# msp430-nrf24.net
KiCad netlist of a schematic drawn in EAGLE
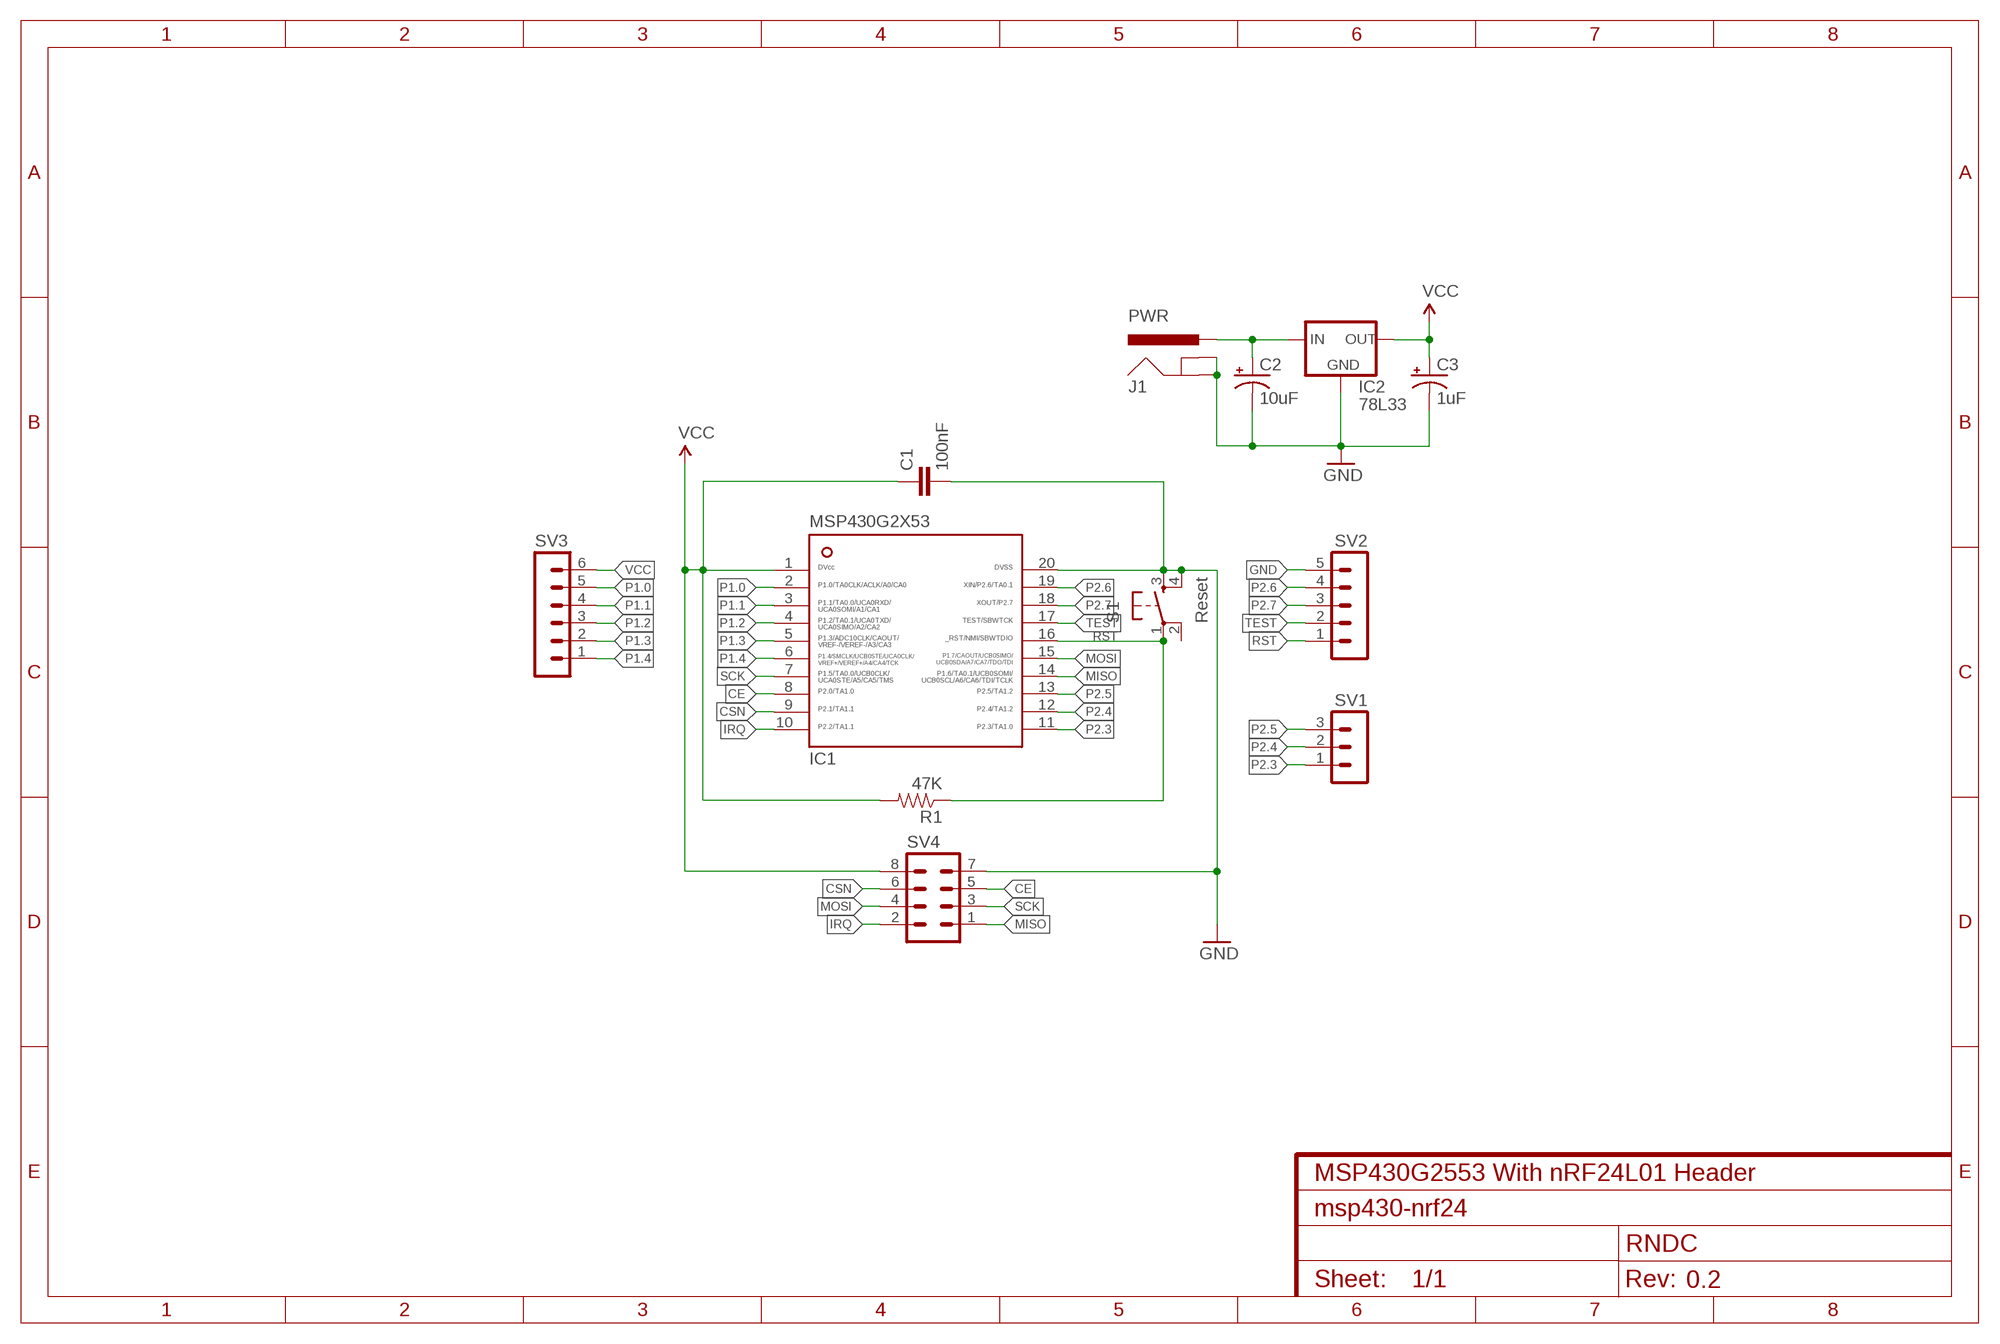
[diagram p0: schematic, sheet 1]

(export (version "E")
  (design (tool "Eeschema 10.0.6"))
  (components
    (comp (ref "C1")
      (value "100nF")
      (footprint "eagle-import:CAP-PTH-SMALL-KIT")
      (libsource (lib "eagle-import") (part "CAPKIT"))
    )
    (comp (ref "C2")
      (value "10uF")
      (footprint "eagle-import:CPOL-RADIAL-10UF-25V")
      (libsource (lib "eagle-import") (part "CAP_POLPTH2"))
    )
    (comp (ref "C3")
      (value "1uF")
      (footprint "eagle-import:CPOL-RADIAL-10UF-25V")
      (libsource (lib "eagle-import") (part "CAP_POLPTH2"))
    )
    (comp (ref "IC1")
      (value "MSP430G2X53-20N20")
      (footprint "eagle-import:N20")
      (libsource (lib "eagle-import") (part "MSP430G2X53-20N20"))
    )
    (comp (ref "IC2")
      (value "78L33")
      (footprint "eagle-import:TO-92")
      (libsource (lib "eagle-import") (part "V_REG_78XXTO-92_UNTESTED"))
    )
    (comp (ref "J1")
      (value "PWR")
      (footprint "eagle-import:POWER_JACK_PTH")
      (libsource (lib "eagle-import") (part "POWER_JACKPTH"))
    )
    (comp (ref "R1")
      (value "47K")
      (footprint "eagle-import:AXIAL-0.3-KIT")
      (libsource (lib "eagle-import") (part "RESISTORKIT"))
    )
    (comp (ref "S1")
      (value "Reset")
      (footprint "eagle-import:TACTILE-PTH")
      (libsource (lib "eagle-import") (part "TAC_SWITCHPTH"))
    )
    (comp (ref "SV1")
      (value "MA03-1")
      (footprint "eagle-import:MA03-1")
      (libsource (lib "eagle-import") (part "MA03-1"))
    )
    (comp (ref "SV2")
      (value "MA05-1")
      (footprint "eagle-import:MA05-1")
      (libsource (lib "eagle-import") (part "MA05-1"))
    )
    (comp (ref "SV3")
      (value "MA06-1")
      (footprint "eagle-import:MA06-1")
      (libsource (lib "eagle-import") (part "MA06-1"))
    )
    (comp (ref "SV4")
      (value "MA04-2")
      (footprint "eagle-import:MA04-2")
      (libsource (lib "eagle-import") (part "MA04-2"))
    )
  )
  (nets
    (net (code "1") (name "CE") (class "Default")
      (node (ref "IC1") (pin "8") (pinfunction "8_8") (pintype "bidirectional"))
      (node (ref "SV4") (pin "5") (pinfunction "5_5") (pintype "passive"))
    )
    (net (code "2") (name "CSN") (class "Default")
      (node (ref "IC1") (pin "9") (pinfunction "9_9") (pintype "bidirectional"))
      (node (ref "SV4") (pin "6") (pinfunction "6_6") (pintype "passive"))
    )
    (net (code "3") (name "GND") (class "Default")
      (node (ref "C1") (pin "2") (pinfunction "2_2") (pintype "passive"))
      (node (ref "C2") (pin "2") (pinfunction "-_2") (pintype "passive"))
      (node (ref "C3") (pin "2") (pinfunction "-_2") (pintype "passive"))
      (node (ref "IC1") (pin "20") (pinfunction "20_20") (pintype "bidirectional"))
      (node (ref "IC2") (pin "1") (pinfunction "GND_1") (pintype "input"))
      (node (ref "J1") (pin "GND") (pinfunction "GND_GND") (pintype "bidirectional"))
      (node (ref "J1") (pin "GNDBREAK") (pinfunction "GNDBREAK_GNDBREAK") (pintype "bidirectional"))
      (node (ref "S1") (pin "3") (pinfunction "3_3") (pintype "passive"))
      (node (ref "S1") (pin "4") (pinfunction "4_4") (pintype "passive"))
      (node (ref "SV2") (pin "5") (pinfunction "5_5") (pintype "passive"))
      (node (ref "SV4") (pin "7") (pinfunction "7_7") (pintype "passive"))
    )
    (net (code "4") (name "IRQ") (class "Default")
      (node (ref "IC1") (pin "10") (pinfunction "10_10") (pintype "bidirectional"))
      (node (ref "SV4") (pin "2") (pinfunction "2_2") (pintype "passive"))
    )
    (net (code "5") (name "MISO") (class "Default")
      (node (ref "IC1") (pin "14") (pinfunction "14_14") (pintype "bidirectional"))
      (node (ref "SV4") (pin "1") (pinfunction "1_1") (pintype "passive"))
    )
    (net (code "6") (name "MOSI") (class "Default")
      (node (ref "IC1") (pin "15") (pinfunction "15_15") (pintype "bidirectional"))
      (node (ref "SV4") (pin "4") (pinfunction "4_4") (pintype "passive"))
    )
    (net (code "7") (name "Net-(C2-+)") (class "Default")
      (node (ref "C2") (pin "1") (pinfunction "+_1") (pintype "passive"))
      (node (ref "IC2") (pin "2") (pinfunction "IN_2") (pintype "input"))
      (node (ref "J1") (pin "PWR") (pinfunction "PWR_PWR") (pintype "bidirectional"))
    )
    (net (code "8") (name "P1.0") (class "Default")
      (node (ref "IC1") (pin "2") (pinfunction "2_2") (pintype "bidirectional"))
      (node (ref "SV3") (pin "5") (pinfunction "5_5") (pintype "passive"))
    )
    (net (code "9") (name "P1.1") (class "Default")
      (node (ref "IC1") (pin "3") (pinfunction "3_3") (pintype "bidirectional"))
      (node (ref "SV3") (pin "4") (pinfunction "4_4") (pintype "passive"))
    )
    (net (code "10") (name "P1.2") (class "Default")
      (node (ref "IC1") (pin "4") (pinfunction "4_4") (pintype "bidirectional"))
      (node (ref "SV3") (pin "3") (pinfunction "3_3") (pintype "passive"))
    )
    (net (code "11") (name "P1.3") (class "Default")
      (node (ref "IC1") (pin "5") (pinfunction "5_5") (pintype "bidirectional"))
      (node (ref "SV3") (pin "2") (pinfunction "2_2") (pintype "passive"))
    )
    (net (code "12") (name "P1.4") (class "Default")
      (node (ref "IC1") (pin "6") (pinfunction "6_6") (pintype "bidirectional"))
      (node (ref "SV3") (pin "1") (pinfunction "1_1") (pintype "passive"))
    )
    (net (code "13") (name "P2.3") (class "Default")
      (node (ref "IC1") (pin "11") (pinfunction "11_11") (pintype "bidirectional"))
      (node (ref "SV1") (pin "1") (pinfunction "1_1") (pintype "passive"))
    )
    (net (code "14") (name "P2.4") (class "Default")
      (node (ref "IC1") (pin "12") (pinfunction "12_12") (pintype "bidirectional"))
      (node (ref "SV1") (pin "2") (pinfunction "2_2") (pintype "passive"))
    )
    (net (code "15") (name "P2.5") (class "Default")
      (node (ref "IC1") (pin "13") (pinfunction "13_13") (pintype "bidirectional"))
      (node (ref "SV1") (pin "3") (pinfunction "3_3") (pintype "passive"))
    )
    (net (code "16") (name "P2.6") (class "Default")
      (node (ref "IC1") (pin "19") (pinfunction "19_19") (pintype "bidirectional"))
      (node (ref "SV2") (pin "4") (pinfunction "4_4") (pintype "passive"))
    )
    (net (code "17") (name "P2.7") (class "Default")
      (node (ref "IC1") (pin "18") (pinfunction "18_18") (pintype "bidirectional"))
      (node (ref "SV2") (pin "3") (pinfunction "3_3") (pintype "passive"))
    )
    (net (code "18") (name "RST") (class "Default")
      (node (ref "IC1") (pin "16") (pinfunction "16_16") (pintype "bidirectional"))
      (node (ref "R1") (pin "P$1") (pinfunction "1_P$1") (pintype "passive"))
      (node (ref "S1") (pin "1") (pinfunction "1_1") (pintype "passive"))
      (node (ref "SV2") (pin "1") (pinfunction "1_1") (pintype "passive"))
    )
    (net (code "19") (name "SCK") (class "Default")
      (node (ref "IC1") (pin "7") (pinfunction "7_7") (pintype "bidirectional"))
      (node (ref "SV4") (pin "3") (pinfunction "3_3") (pintype "passive"))
    )
    (net (code "20") (name "TEST") (class "Default")
      (node (ref "IC1") (pin "17") (pinfunction "17_17") (pintype "bidirectional"))
      (node (ref "SV2") (pin "2") (pinfunction "2_2") (pintype "passive"))
    )
    (net (code "21") (name "VCC") (class "Default")
      (node (ref "C1") (pin "1") (pinfunction "1_1") (pintype "passive"))
      (node (ref "C3") (pin "1") (pinfunction "+_1") (pintype "passive"))
      (node (ref "IC1") (pin "1") (pinfunction "1_1") (pintype "bidirectional"))
      (node (ref "IC2") (pin "3") (pinfunction "OUT_3") (pintype "output"))
      (node (ref "R1") (pin "P$2") (pinfunction "2_P$2") (pintype "passive"))
      (node (ref "SV3") (pin "6") (pinfunction "6_6") (pintype "passive"))
      (node (ref "SV4") (pin "8") (pinfunction "8_8") (pintype "passive"))
    )
    (net (code "22") (name "unconnected-(S1-Pad2)") (class "Default")
      (node (ref "S1") (pin "2") (pinfunction "2_2") (pintype "passive"))
    )
  )
)
